# dubBoardScratch.net
KiCad netlist of a schematic drawn in EAGLE
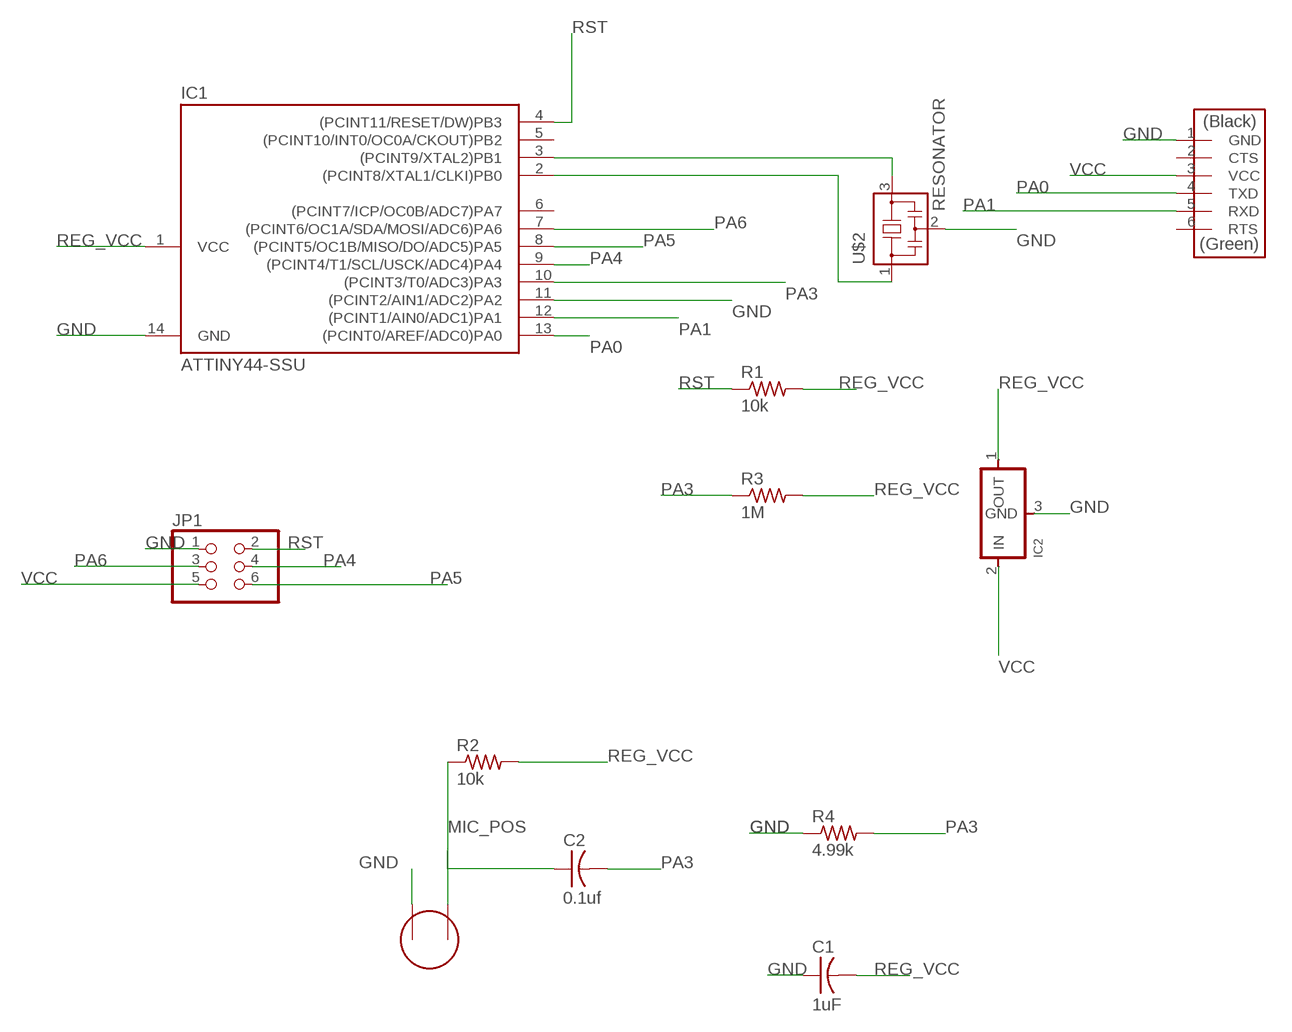
[diagram p0: schematic, sheet 1]

(export (version "E")
  (design (tool "Eeschema 10.0.6"))
  (components
    (comp (ref "C1")
      (value "1uF")
      (footprint "eagle-import:C1206FAB")
      (libsource (lib "eagle-import") (part "CAP-US1206FAB"))
    )
    (comp (ref "C2")
      (value "0.1uf")
      (footprint "eagle-import:C1206FAB")
      (libsource (lib "eagle-import") (part "CAP-US1206FAB"))
    )
    (comp (ref "IC1")
      (value "ATTINY44-SSU")
      (footprint "eagle-import:SOIC14")
      (libsource (lib "eagle-import") (part "ATTINY44-SSU"))
    )
    (comp (ref "IC2")
      (value "REGULATORSOT23")
      (footprint "eagle-import:SOT23")
      (libsource (lib "eagle-import") (part "REGULATORSOT23"))
    )
    (comp (ref "JP1")
      (value "PINHD-2X3-SMD")
      (footprint "eagle-import:2X03SMD")
      (libsource (lib "eagle-import") (part "PINHD-2X3-SMD"))
    )
    (comp (ref "R1")
      (value "10k")
      (footprint "eagle-import:R1206FAB")
      (libsource (lib "eagle-import") (part "RES-US1206FAB"))
    )
    (comp (ref "R2")
      (value "10k")
      (footprint "eagle-import:R1206FAB")
      (libsource (lib "eagle-import") (part "RES-US1206FAB"))
    )
    (comp (ref "R3")
      (value "1M")
      (footprint "eagle-import:R1206FAB")
      (libsource (lib "eagle-import") (part "RES-US1206FAB"))
    )
    (comp (ref "R4")
      (value "4.99k")
      (footprint "eagle-import:R1206FAB")
      (libsource (lib "eagle-import") (part "RES-US1206FAB"))
    )
    (comp (ref "U$1")
      (value "FTDI-SMD-HEADER")
      (footprint "eagle-import:1X06SMD")
      (libsource (lib "eagle-import") (part "FTDI-SMD-HEADER"))
    )
    (comp (ref "U$2")
      (value "RESONATOR")
      (footprint "eagle-import:EFOBM")
      (libsource (lib "eagle-import") (part "RESONATOR"))
    )
    (comp (ref "U$3")
      (value "ELECTRET")
      (footprint "eagle-import:ELECTRET_2742PBJ-A")
      (libsource (lib "eagle-import") (part "ELECTRET"))
    )
  )
  (nets
    (net (code "1") (name "/GND") (class "Default")
      (node (ref "C1") (pin "1") (pinfunction "1_1") (pintype "passive"))
      (node (ref "IC1") (pin "11") (pinfunction "(PCINT2/AIN1/ADC2)PA2_11") (pintype "bidirectional"))
      (node (ref "IC1") (pin "14") (pinfunction "GND_14") (pintype "power_in"))
      (node (ref "IC2") (pin "3") (pinfunction "GND_3") (pintype "bidirectional"))
      (node (ref "JP1") (pin "1") (pinfunction "1_1") (pintype "passive"))
      (node (ref "R4") (pin "1") (pinfunction "1_1") (pintype "passive"))
      (node (ref "U$1") (pin "1") (pinfunction "GND_1") (pintype "bidirectional"))
      (node (ref "U$2") (pin "2") (pinfunction "2_2") (pintype "passive"))
      (node (ref "U$3") (pin "P$2") (pinfunction "P$2_P$2") (pintype "bidirectional"))
    )
    (net (code "2") (name "/MIC_POS") (class "Default")
      (node (ref "C2") (pin "1") (pinfunction "1_1") (pintype "passive"))
      (node (ref "R2") (pin "1") (pinfunction "1_1") (pintype "passive"))
      (node (ref "U$3") (pin "P$1") (pinfunction "P$1_P$1") (pintype "bidirectional"))
    )
    (net (code "3") (name "/PA0") (class "Default")
      (node (ref "IC1") (pin "13") (pinfunction "(PCINT0/AREF/ADC0)PA0_13") (pintype "bidirectional"))
      (node (ref "U$1") (pin "4") (pinfunction "TXD_4") (pintype "bidirectional"))
    )
    (net (code "4") (name "/PA1") (class "Default")
      (node (ref "IC1") (pin "12") (pinfunction "(PCINT1/AIN0/ADC1)PA1_12") (pintype "bidirectional"))
      (node (ref "U$1") (pin "5") (pinfunction "RXD_5") (pintype "bidirectional"))
    )
    (net (code "5") (name "/PA3") (class "Default")
      (node (ref "C2") (pin "2") (pinfunction "2_2") (pintype "passive"))
      (node (ref "IC1") (pin "10") (pinfunction "(PCINT3/T0/ADC3)PA3_10") (pintype "bidirectional"))
      (node (ref "R3") (pin "1") (pinfunction "1_1") (pintype "passive"))
      (node (ref "R4") (pin "2") (pinfunction "2_2") (pintype "passive"))
    )
    (net (code "6") (name "/PA4") (class "Default")
      (node (ref "IC1") (pin "9") (pinfunction "(PCINT4/T1/SCL/USCK/ADC4)PA4_9") (pintype "bidirectional"))
      (node (ref "JP1") (pin "4") (pinfunction "4_4") (pintype "passive"))
    )
    (net (code "7") (name "/PA5") (class "Default")
      (node (ref "IC1") (pin "8") (pinfunction "(PCINT5/OC1B/MISO/DO/ADC5)PA5_8") (pintype "bidirectional"))
      (node (ref "JP1") (pin "6") (pinfunction "6_6") (pintype "passive"))
    )
    (net (code "8") (name "/PA6") (class "Default")
      (node (ref "IC1") (pin "7") (pinfunction "(PCINT6/OC1A/SDA/MOSI/ADC6)PA6_7") (pintype "bidirectional"))
      (node (ref "JP1") (pin "3") (pinfunction "3_3") (pintype "passive"))
    )
    (net (code "9") (name "/REG_VCC") (class "Default")
      (node (ref "C1") (pin "2") (pinfunction "2_2") (pintype "passive"))
      (node (ref "IC1") (pin "1") (pinfunction "VCC_1") (pintype "power_in"))
      (node (ref "IC2") (pin "1") (pinfunction "OUT_1") (pintype "bidirectional"))
      (node (ref "R1") (pin "2") (pinfunction "2_2") (pintype "passive"))
      (node (ref "R2") (pin "2") (pinfunction "2_2") (pintype "passive"))
      (node (ref "R3") (pin "2") (pinfunction "2_2") (pintype "passive"))
    )
    (net (code "10") (name "/RST") (class "Default")
      (node (ref "IC1") (pin "4") (pinfunction "(PCINT11/RESET/DW)PB3_4") (pintype "bidirectional"))
      (node (ref "JP1") (pin "2") (pinfunction "2_2") (pintype "passive"))
      (node (ref "R1") (pin "1") (pinfunction "1_1") (pintype "passive"))
    )
    (net (code "11") (name "/VCC") (class "Default")
      (node (ref "IC2") (pin "2") (pinfunction "IN_2") (pintype "bidirectional"))
      (node (ref "JP1") (pin "5") (pinfunction "5_5") (pintype "passive"))
      (node (ref "U$1") (pin "3") (pinfunction "VCC_3") (pintype "bidirectional"))
    )
    (net (code "12") (name "Net-(IC1-(PCINT8{slash}XTAL1{slash}CLKI)PB0)") (class "Default")
      (node (ref "IC1") (pin "2") (pinfunction "(PCINT8/XTAL1/CLKI)PB0_2") (pintype "bidirectional"))
      (node (ref "U$2") (pin "1") (pinfunction "1_1") (pintype "passive"))
    )
    (net (code "13") (name "Net-(IC1-(PCINT9{slash}XTAL2)PB1)") (class "Default")
      (node (ref "IC1") (pin "3") (pinfunction "(PCINT9/XTAL2)PB1_3") (pintype "bidirectional"))
      (node (ref "U$2") (pin "3") (pinfunction "3_3") (pintype "passive"))
    )
    (net (code "14") (name "unconnected-(IC1-(PCINT7{slash}ICP{slash}OC0B{slash}ADC7)PA7-Pad6)") (class "Default")
      (node (ref "IC1") (pin "6") (pinfunction "(PCINT7/ICP/OC0B/ADC7)PA7_6") (pintype "bidirectional"))
    )
    (net (code "15") (name "unconnected-(IC1-(PCINT10{slash}INT0{slash}OC0A{slash}CKOUT)PB2-Pad5)") (class "Default")
      (node (ref "IC1") (pin "5") (pinfunction "(PCINT10/INT0/OC0A/CKOUT)PB2_5") (pintype "bidirectional"))
    )
    (net (code "16") (name "unconnected-(U$1-CTS-Pad2)") (class "Default")
      (node (ref "U$1") (pin "2") (pinfunction "CTS_2") (pintype "bidirectional"))
    )
    (net (code "17") (name "unconnected-(U$1-RTS-Pad6)") (class "Default")
      (node (ref "U$1") (pin "6") (pinfunction "RTS_6") (pintype "bidirectional"))
    )
  )
)
